# ST_LINK_V2-1_2.net
KiCad netlist of a schematic drawn in Altium Designer
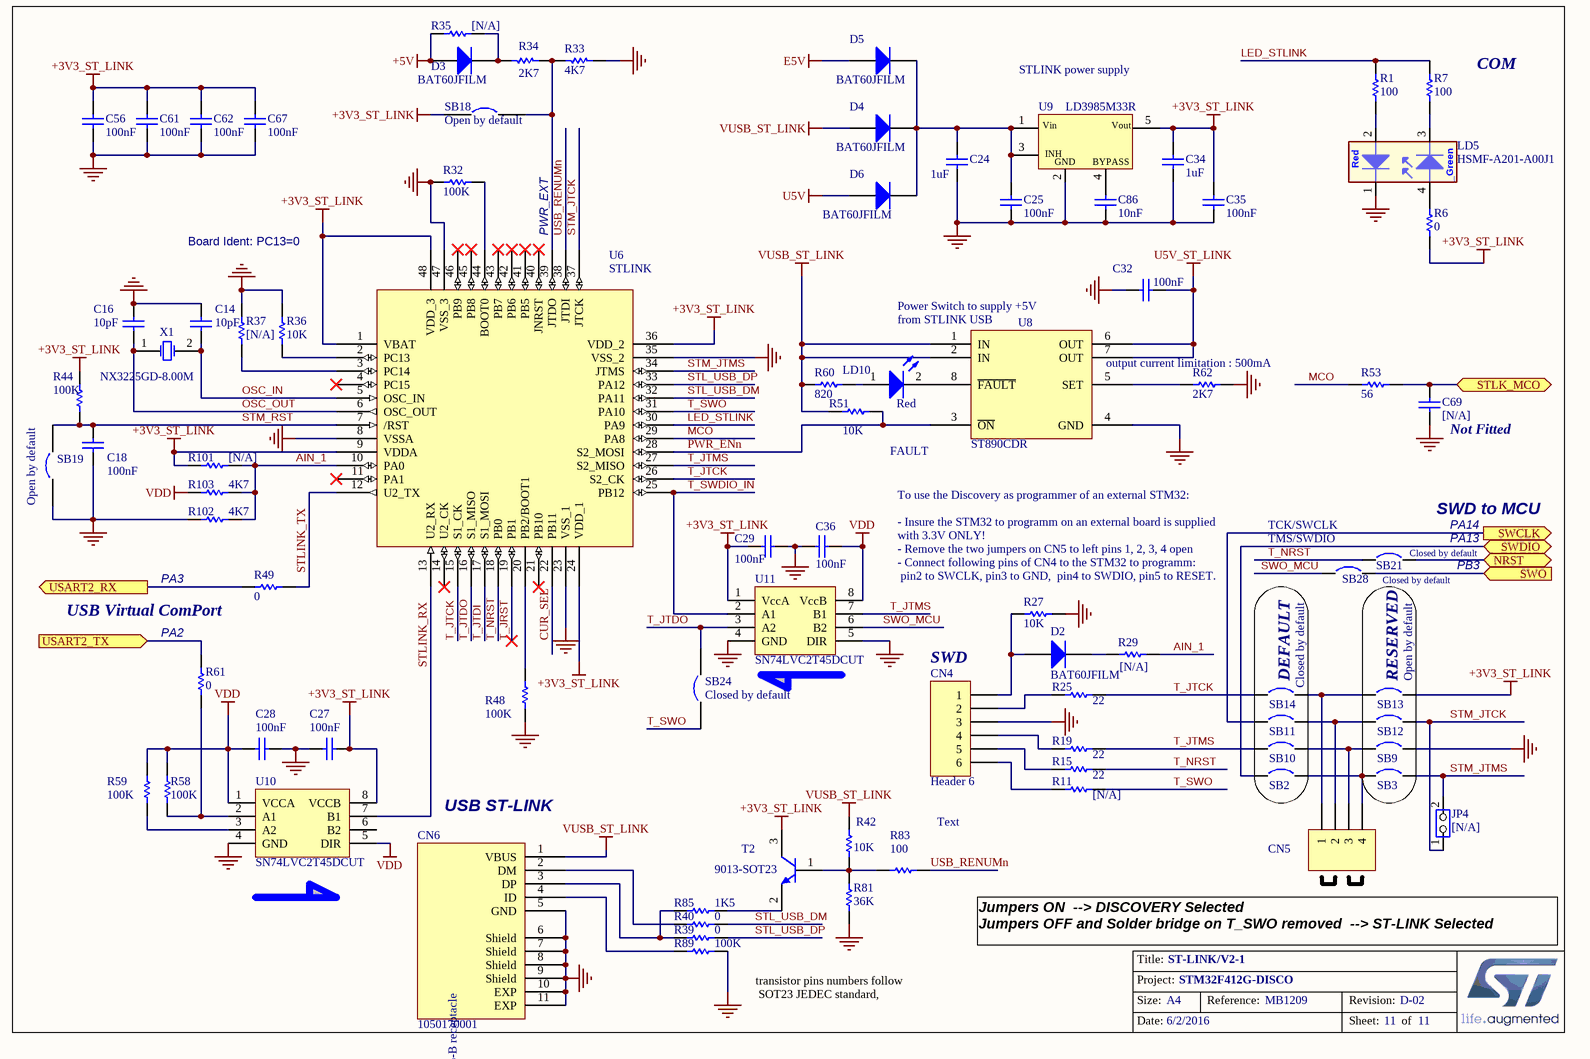
[diagram p0: ST_LINK_V2-1_2.SCHDOC]

(export (version "E")
  (design (tool "Eeschema 10.0.6"))
  (components
    (comp (ref "C14")
      (value "10pF")
      (footprint "0603C")
      (description "Capacitor 0402 / 0603 / 0805")
      (libsource (lib "MCD_TOOLS") (part "Capacitor_ST"))
    )
    (comp (ref "C16")
      (value "10pF")
      (footprint "0603C")
      (description "Capacitor 0402 / 0603 / 0805")
      (libsource (lib "MCD_TOOLS") (part "Capacitor_ST"))
    )
    (comp (ref "C18")
      (value "100nF")
      (footprint "0402C")
      (description "Capacitor 0402 / 0603 / 0805")
      (libsource (lib "MCD_TOOLS") (part "Capacitor_ST"))
    )
    (comp (ref "C24")
      (value "1uF")
      (footprint "0603C")
      (description "Capacitor")
      (fields (field (name "TOLERANCE") "10%"))
      (libsource (lib "MB963_1") (part "CAP SMD 0603  X5R 1µF 25V 10%"))
    )
    (comp (ref "C25")
      (value "100nF")
      (footprint "0402C")
      (description "Capacitor 0402 / 0603 / 0805")
      (libsource (lib "MCD_TOOLS") (part "Capacitor_ST"))
    )
    (comp (ref "C27")
      (value "100nF")
      (footprint "0402C")
      (description "Capacitor")
      (fields (field (name "PUBLISHER") "Altium Limited"))
      (libsource (lib "Miscellaneous Devices") (part "CAP"))
    )
    (comp (ref "C28")
      (value "100nF")
      (footprint "0402C")
      (description "Capacitor")
      (fields (field (name "PUBLISHER") "Altium Limited"))
      (libsource (lib "Miscellaneous Devices") (part "CAP"))
    )
    (comp (ref "C29")
      (value "100nF")
      (footprint "0402C")
      (description "Capacitor")
      (fields (field (name "PUBLISHER") "Altium Limited"))
      (libsource (lib "Miscellaneous Devices") (part "CAP"))
    )
    (comp (ref "C32")
      (value "100nF")
      (footprint "0402C")
      (description "Capacitor 0402 / 0603 / 0805")
      (libsource (lib "MCD_TOOLS") (part "Capacitor_ST"))
    )
    (comp (ref "C34")
      (value "1uF")
      (footprint "0603C")
      (description "Capacitor")
      (fields (field (name "TOLERANCE") "10%"))
      (libsource (lib "MB963_1") (part "CAP SMD 0603  X5R 1µF 25V 10%"))
    )
    (comp (ref "C35")
      (value "100nF")
      (footprint "0402C")
      (description "Capacitor 0402 / 0603 / 0805")
      (libsource (lib "MCD_TOOLS") (part "Capacitor_ST"))
    )
    (comp (ref "C36")
      (value "100nF")
      (footprint "0402C")
      (description "Capacitor")
      (fields (field (name "PUBLISHER") "Altium Limited"))
      (libsource (lib "Miscellaneous Devices") (part "CAP"))
    )
    (comp (ref "C56")
      (value "100nF")
      (footprint "0402C")
      (description "Capacitor 0402 / 0603 / 0805")
      (libsource (lib "MCD_TOOLS") (part "Capacitor_ST"))
    )
    (comp (ref "C61")
      (value "100nF")
      (footprint "0402C")
      (description "Capacitor 0402 / 0603 / 0805")
      (libsource (lib "MCD_TOOLS") (part "Capacitor_ST"))
    )
    (comp (ref "C62")
      (value "100nF")
      (footprint "0402C")
      (description "Capacitor 0402 / 0603 / 0805")
      (libsource (lib "MCD_TOOLS") (part "Capacitor_ST"))
    )
    (comp (ref "C67")
      (value "100nF")
      (footprint "0402C")
      (description "Capacitor 0402 / 0603 / 0805")
      (libsource (lib "MCD_TOOLS") (part "Capacitor_ST"))
    )
    (comp (ref "C69")
      (value "[N/A]")
      (footprint "0603C")
      (description "Capacitor,20pF,50V,NPO,5%,0402,YAGEO")
      (libsource (lib "MCD_TOOLS") (part "Cap_20pF_NPO_5%_0402"))
    )
    (comp (ref "C86")
      (value "10nF")
      (footprint "0603C")
      (description "0603  X7R 10NF")
      (fields (field (name "TOLERANCE") "10%"))
      (libsource (lib "MB963_1") (part "CAP SMD 0603  X7R 10000PF 50V 10%"))
    )
    (comp (ref "CN4")
      (value "Header 6")
      (footprint "HDR_1X6_2R54_W")
      (description "Header, 6-Pin")
      (fields (field (name "PUBLISHER") "Altium Limited"))
      (libsource (lib "Miscellaneous Connectors") (part "Header 6"))
    )
    (comp (ref "CN5")
      (value "Header 4")
      (footprint "HDR_1X4_2R54_W")
      (description "Header, 4-Pin")
      (fields (field (name "PUBLISHER") "Altium Limited"))
      (libsource (lib "MB963_1") (part "Header 4"))
    )
    (comp (ref "CN6")
      (value "1050170001")
      (footprint "Molex_1050170001")
      (libsource (lib "Smartphone_accessory") (part "1050170001"))
    )
    (comp (ref "D2")
      (value "BAT60JFILM")
      (footprint "SOD-323")
      (libsource (lib "MCD_TOOLS") (part "BAT60JFILM"))
    )
    (comp (ref "D3")
      (value "BAT60JFILM")
      (footprint "SOD-323")
      (libsource (lib "MCD_TOOLS") (part "BAT60JFILM"))
    )
    (comp (ref "D4")
      (value "BAT60JFILM")
      (footprint "SOD-323")
      (libsource (lib "MCD_TOOLS") (part "BAT60JFILM"))
    )
    (comp (ref "D5")
      (value "BAT60JFILM")
      (footprint "SOD-323")
      (libsource (lib "MCD_TOOLS") (part "BAT60JFILM"))
    )
    (comp (ref "D6")
      (value "BAT60JFILM")
      (footprint "SOD-323")
      (libsource (lib "MCD_TOOLS") (part "BAT60JFILM"))
    )
    (comp (ref "JP4") (value "[N/A]") (footprint "SIP2") (libsource (lib "Almos") (part "JP2")))
    (comp (ref "LD5")
      (value "HSMF-A201-A00J1")
      (footprint "LED2_3528")
      (description "Bicolor Led")
      (libsource (lib "MCD_TOOLS") (part "LD_BICOLOR_CMS"))
    )
    (comp (ref "LD10")
      (value "Red")
      (footprint "0603D")
      (description "Typical RED, GREEN, YELLOW, AMBER GaAs LED")
      (fields (field (name "SILKSCREEN") "FAULT") (field (name "PUBLISHER") "Altium Limited"))
      (libsource (lib "Miscellaneous Devices") (part "LED2"))
    )
    (comp (ref "R1")
      (value "100")
      (footprint "0402R")
      (description "Resistor")
      (fields (field (name "PUBLISHER") "Altium Limited"))
      (libsource (lib "") (part "Res1_1"))
    )
    (comp (ref "R6")
      (value "0")
      (footprint "SB_0603")
      (description "Resistor")
      (fields (field (name "PUBLISHER") "Altium Limited"))
      (libsource (lib "") (part "Res1_1"))
    )
    (comp (ref "R7")
      (value "100")
      (footprint "0402R")
      (description "Resistor")
      (fields (field (name "PUBLISHER") "Altium Limited"))
      (libsource (lib "") (part "Res1_1"))
    )
    (comp (ref "R11")
      (value "[N/A]")
      (footprint "0402R")
      (description "Resistor")
      (fields (field (name "PUBLISHER") "Altium Limited"))
      (libsource (lib "MB915_1") (part "res1"))
    )
    (comp (ref "R15")
      (value "22")
      (footprint "0402R")
      (description "Resistor")
      (fields (field (name "PUBLISHER") "Altium Limited"))
      (libsource (lib "MB915_1") (part "res1"))
    )
    (comp (ref "R19")
      (value "22")
      (footprint "0402R")
      (description "Resistor")
      (fields (field (name "PUBLISHER") "Altium Limited"))
      (libsource (lib "MB915_1") (part "res1"))
    )
    (comp (ref "R25")
      (value "22")
      (footprint "0402R")
      (description "Resistor")
      (fields (field (name "PUBLISHER") "Altium Limited"))
      (libsource (lib "MB915_1") (part "res1"))
    )
    (comp (ref "R27")
      (value "10K")
      (footprint "0402R")
      (description "Resistor")
      (fields (field (name "PUBLISHER") "Altium Limited"))
      (libsource (lib "MB915_1") (part "res1"))
    )
    (comp (ref "R29")
      (value "[N/A]")
      (footprint "STM-SMEE:0402R")
      (description "Resistor,[NA],0402")
      (libsource (lib "MCD_TOOLS") (part "Res_NA_0402"))
    )
    (comp (ref "R32")
      (value "100K")
      (footprint "0402R")
      (description "Resistor 0402 / 0603 / 0805")
      (libsource (lib "Miscellaneous Devices") (part "Res1"))
    )
    (comp (ref "R33")
      (value "4K7")
      (footprint "0603R")
      (description "Resistor")
      (fields (field (name "PUBLISHER") "Altium Limited"))
      (libsource (lib "") (part "Res1_2"))
    )
    (comp (ref "R34")
      (value "2K7")
      (footprint "0603R")
      (description "Resistor")
      (fields (field (name "PUBLISHER") "Altium Limited"))
      (libsource (lib "") (part "Res1_2"))
    )
    (comp (ref "R35")
      (value "[N/A]")
      (footprint "0402R")
      (description "Resistor")
      (libsource (lib "MCD_TOOLS") (part "Resistor_ST"))
    )
    (comp (ref "R36")
      (value "10K")
      (footprint "0402R")
      (description "Resistor")
      (libsource (lib "Miscellaneous Devices") (part "Res1"))
    )
    (comp (ref "R37")
      (value "[N/A]")
      (footprint "0603R")
      (description "Resistor 0402 / 0603 / 0805")
      (libsource (lib "Miscellaneous Devices") (part "Res1"))
    )
    (comp (ref "R39")
      (value "0")
      (footprint "SB_0603")
      (description "Resistor")
      (libsource (lib "Miscellaneous Devices") (part "Res1"))
    )
    (comp (ref "R40")
      (value "0")
      (footprint "SB_0603")
      (description "Resistor")
      (libsource (lib "Miscellaneous Devices") (part "Res1"))
    )
    (comp (ref "R42")
      (value "10K")
      (footprint "0402R")
      (description "Resistor")
      (fields (field (name "PUBLISHER") "Altium Limited"))
      (libsource (lib "") (part "Res1_1"))
    )
    (comp (ref "R44")
      (value "100K")
      (footprint "0402R")
      (description "Resistor 0402 / 0603 / 0805")
      (libsource (lib "Miscellaneous Devices") (part "Res1"))
    )
    (comp (ref "R48")
      (value "100K")
      (footprint "0402R")
      (description "Resistor 0402 / 0603 / 0805")
      (libsource (lib "Miscellaneous Devices") (part "Res1"))
    )
    (comp (ref "R49")
      (value "0")
      (footprint "SB_0603")
      (description "Resistor")
      (fields (field (name "PUBLISHER") "Altium Limited"))
      (libsource (lib "") (part "Res1_1"))
    )
    (comp (ref "R51")
      (value "10K")
      (footprint "0402R")
      (description "Resistor")
      (libsource (lib "MCD_TOOLS") (part "Resistor_ST"))
    )
    (comp (ref "R53")
      (value "56")
      (footprint "0603R")
      (description "Resistor")
      (fields (field (name "PUBLISHER") "Altium Limited"))
      (libsource (lib "") (part "Res1_1"))
    )
    (comp (ref "R58")
      (value "100K")
      (footprint "0402R")
      (description "Resistor")
      (fields (field (name "PUBLISHER") "Altium Limited"))
      (libsource (lib "") (part "Res1_1"))
    )
    (comp (ref "R59")
      (value "100K")
      (footprint "0402R")
      (description "Resistor")
      (fields (field (name "PUBLISHER") "Altium Limited"))
      (libsource (lib "") (part "Res1_1"))
    )
    (comp (ref "R60")
      (value "820")
      (footprint "0402R")
      (description "Resistor")
      (fields (field (name "PUBLISHER") "Altium Limited"))
      (libsource (lib "Miscellaneous Devices") (part "res1"))
    )
    (comp (ref "R61")
      (value "0")
      (footprint "SB_0603")
      (description "Resistor")
      (fields (field (name "PUBLISHER") "Altium Limited"))
      (libsource (lib "") (part "Res1_1"))
    )
    (comp (ref "R62")
      (value "2K7")
      (footprint "STM-SMEE:0603R")
      (description "Resistor 0402 / 0603 / 0805")
      (libsource (lib "MCD_TOOLS") (part "Resistor_ST"))
    )
    (comp (ref "R81")
      (value "36K")
      (footprint "0603R")
      (description "Resistor")
      (fields (field (name "PUBLISHER") "Altium Limited"))
      (libsource (lib "") (part "Res1_1"))
    )
    (comp (ref "R83")
      (value "100")
      (footprint "0402R")
      (description "Resistor 0402 / 0603 / 0805")
      (libsource (lib "Miscellaneous Devices") (part "Res1"))
    )
    (comp (ref "R85")
      (value "1K5")
      (footprint "0603R")
      (description "Resistor")
      (libsource (lib "Miscellaneous Devices") (part "Res1"))
    )
    (comp (ref "R89")
      (value "100K")
      (footprint "0402R")
      (description "Resistor")
      (fields (field (name "PUBLISHER") "Altium Limited"))
      (libsource (lib "Miscellaneous Devices") (part "res1"))
    )
    (comp (ref "R101")
      (value "[N/A]")
      (footprint "0603R")
      (description "Resistor 0402 / 0603 / 0805")
      (libsource (lib "Miscellaneous Devices") (part "Res1"))
    )
    (comp (ref "R102")
      (value "4K7")
      (footprint "0603R")
      (description "Resistor 0402 / 0603 / 0805")
      (libsource (lib "Miscellaneous Devices") (part "Res1"))
    )
    (comp (ref "R103")
      (value "4K7")
      (footprint "0603R")
      (description "Resistor 0402 / 0603 / 0805")
      (libsource (lib "Miscellaneous Devices") (part "Res1"))
    )
    (comp (ref "SB2")
      (value "Closed by default")
      (footprint "SB_0603")
      (description "Circuit Breaker")
      (libsource (lib "MCD_TOOLS") (part "Circuit Breaker"))
    )
    (comp (ref "SB3")
      (value "Open by default")
      (footprint "SB_0603")
      (description "Circuit Breaker")
      (libsource (lib "MCD_TOOLS") (part "Circuit Breaker"))
    )
    (comp (ref "SB9")
      (value "Open by default")
      (footprint "SB_0603")
      (description "Circuit Breaker")
      (libsource (lib "MCD_TOOLS") (part "Circuit Breaker"))
    )
    (comp (ref "SB10")
      (value "Closed by default")
      (footprint "SB_0603")
      (description "Circuit Breaker")
      (libsource (lib "MCD_TOOLS") (part "Circuit Breaker"))
    )
    (comp (ref "SB11")
      (value "Closed by default")
      (footprint "SB_0603")
      (description "Circuit Breaker")
      (libsource (lib "MCD_TOOLS") (part "Circuit Breaker"))
    )
    (comp (ref "SB12")
      (value "Open by default")
      (footprint "SB_0603")
      (description "Circuit Breaker")
      (libsource (lib "MCD_TOOLS") (part "Circuit Breaker"))
    )
    (comp (ref "SB13")
      (value "Open by default")
      (footprint "SB_0603")
      (description "Circuit Breaker")
      (libsource (lib "MCD_TOOLS") (part "Circuit Breaker"))
    )
    (comp (ref "SB14")
      (value "Closed by default")
      (footprint "SB_0603")
      (description "Circuit Breaker")
      (libsource (lib "MCD_TOOLS") (part "Circuit Breaker"))
    )
    (comp (ref "SB18")
      (value "Open by default")
      (footprint "SB_0603")
      (description "Circuit Breaker")
      (fields (field (name "PUBLISHER") "Altium Limited"))
      (libsource (lib "Miscellaneous Devices") (part "Circuit Breaker"))
    )
    (comp (ref "SB19")
      (value "Open by default")
      (footprint "SB_0603")
      (description "Circuit Breaker")
      (fields (field (name "PUBLISHER") "Altium Limited"))
      (libsource (lib "Miscellaneous Devices") (part "Circuit Breaker"))
    )
    (comp (ref "SB21")
      (value "Closed by default")
      (footprint "SB_0603")
      (description "Circuit Breaker")
      (libsource (lib "MCD_TOOLS") (part "Circuit Breaker"))
    )
    (comp (ref "SB24")
      (value "Closed by default")
      (footprint "SB_0603")
      (description "Circuit Breaker")
      (fields (field (name "PUBLISHER") "Altium Limited"))
      (libsource (lib "Miscellaneous Devices") (part "Circuit Breaker"))
    )
    (comp (ref "SB28")
      (value "Closed by default")
      (footprint "SB_0603")
      (description "Circuit Breaker")
      (libsource (lib "MCD_TOOLS") (part "Circuit Breaker"))
    )
    (comp (ref "T2")
      (value "9013-SOT23")
      (footprint "SOT-23")
      (description "NPN Bipolar Transistor")
      (fields (field (name "PUBLISHER") "Altium Limited"))
      (libsource (lib "MB1167") (part "NPN"))
    )
    (comp (ref "U6")
      (value "STLINK")
      (footprint "LQFP48_0R5_9X9")
      (libsource (lib "*") (part "STM32F10x(48pin)"))
    )
    (comp (ref "U8")
      (value "ST890CDR")
      (footprint "SOIC8_1R27_4R9X6")
      (libsource (lib "MB1167") (part "ST890CDR"))
    )
    (comp (ref "U9")
      (value "LD3985M33R")
      (footprint "SOT23-5")
      (description "Ultra low drop-low noise BiCMOS voltage, regulators low ESR capacitors compatible")
      (libsource (lib "MCD_TOOLS") (part "LD3985M33R"))
    )
    (comp (ref "U10")
      (value "SN74LVC2T45DCUT")
      (footprint "USOP8_0R5_2X3R1")
      (libsource (lib "MB818") (part "SN74LVC2T45DCUT"))
    )
    (comp (ref "U11")
      (value "SN74LVC2T45DCUT")
      (footprint "USOP8_0R5_2X3R1")
      (libsource (lib "STLINK") (part "SN74LVC2T45DCUT"))
    )
    (comp (ref "X1")
      (value "NX3225GD-8.00M")
      (footprint "XTAL_2SM_3R2X2R5")
      (description "Crystal 8Mhz, 8pF, -+50PPM, SMD")
      (libsource (lib "MCD_TOOLS") (part "XTAL_8M_NX3225GD"))
    )
  )
  (nets
    (net (code "1") (name "+3V3_ST_LINK") (class "Default")
      (node (ref "C27") (pin "1") (pinfunction "1_1") (pintype "passive"))
      (node (ref "C29") (pin "1") (pinfunction "1_1") (pintype "passive"))
      (node (ref "C34") (pin "1") (pinfunction "1_1") (pintype "passive"))
      (node (ref "C35") (pin "2") (pinfunction "2_2") (pintype "passive"))
      (node (ref "C56") (pin "2") (pinfunction "2_2") (pintype "passive"))
      (node (ref "C61") (pin "2") (pinfunction "2_2") (pintype "passive"))
      (node (ref "C62") (pin "2") (pinfunction "2_2") (pintype "passive"))
      (node (ref "C67") (pin "2") (pinfunction "2_2") (pintype "passive"))
      (node (ref "R101") (pin "1") (pinfunction "1_1") (pintype "passive"))
      (node (ref "R44") (pin "2") (pinfunction "2_2") (pintype "passive"))
      (node (ref "R6") (pin "2") (pinfunction "2_2") (pintype "passive"))
      (node (ref "SB13") (pin "2") (pinfunction "2_2") (pintype "passive"))
      (node (ref "SB18") (pin "1") (pinfunction "1_1") (pintype "passive"))
      (node (ref "T2") (pin "3") (pinfunction "C_3") (pintype "passive"))
      (node (ref "U10") (pin "8") (pinfunction "VCCB_8") (pintype "passive"))
      (node (ref "U11") (pin "1") (pinfunction "VccA_1") (pintype "passive"))
      (node (ref "U6") (pin "1") (pinfunction "VBAT_1") (pintype "power_in"))
      (node (ref "U6") (pin "24") (pinfunction "VDD_1_24") (pintype "power_in"))
      (node (ref "U6") (pin "36") (pinfunction "VDD_2_36") (pintype "power_in"))
      (node (ref "U6") (pin "48") (pinfunction "VDD_3_48") (pintype "power_in"))
      (node (ref "U6") (pin "9") (pinfunction "VDDA_9") (pintype "power_in"))
      (node (ref "U9") (pin "5") (pinfunction "Vout_5") (pintype "passive"))
    )
    (net (code "2") (name "+5V") (class "Default")
      (node (ref "D3") (pin "1") (pinfunction "A_1") (pintype "passive"))
      (node (ref "R35") (pin "1") (pinfunction "1_1") (pintype "passive"))
    )
    (net (code "3") (name "/AIN_1") (class "Default")
      (node (ref "R101") (pin "2") (pinfunction "2_2") (pintype "passive"))
      (node (ref "R102") (pin "2") (pinfunction "2_2") (pintype "passive"))
      (node (ref "R103") (pin "2") (pinfunction "2_2") (pintype "passive"))
      (node (ref "R29") (pin "2") (pinfunction "2_2") (pintype "passive"))
      (node (ref "U6") (pin "10") (pinfunction "PA0_10") (pintype "bidirectional"))
    )
    (net (code "4") (name "/CUR_SEL") (class "Default")
      (node (ref "U6") (pin "22") (pinfunction "PB11_22") (pintype "passive"))
    )
    (net (code "5") (name "/LED_STLINK") (class "Default")
      (node (ref "R1") (pin "1") (pinfunction "1_1") (pintype "passive"))
      (node (ref "R7") (pin "1") (pinfunction "1_1") (pintype "passive"))
      (node (ref "U6") (pin "30") (pinfunction "PA9_30") (pintype "bidirectional"))
    )
    (net (code "6") (name "/MCO") (class "Default")
      (node (ref "R53") (pin "2") (pinfunction "2_2") (pintype "passive"))
      (node (ref "U6") (pin "29") (pinfunction "PA8_29") (pintype "bidirectional"))
    )
    (net (code "7") (name "/NRST") (class "Default")
      (node (ref "SB21") (pin "2") (pinfunction "2_2") (pintype "passive"))
    )
    (net (code "8") (name "/OSC_IN") (class "Default")
      (node (ref "C14") (pin "1") (pinfunction "1_1") (pintype "passive"))
      (node (ref "U6") (pin "5") (pinfunction "OSC_IN_5") (pintype "input"))
      (node (ref "X1") (pin "2") (pinfunction "OSC2_2") (pintype "passive"))
    )
    (net (code "9") (name "/OSC_OUT") (class "Default")
      (node (ref "C16") (pin "1") (pinfunction "1_1") (pintype "passive"))
      (node (ref "U6") (pin "6") (pinfunction "OSC_OUT_6") (pintype "output"))
      (node (ref "X1") (pin "1") (pinfunction "OSC1_1") (pintype "passive"))
    )
    (net (code "10") (name "/PWR_ENn") (class "Default")
      (node (ref "R51") (pin "2") (pinfunction "2_2") (pintype "passive"))
      (node (ref "U6") (pin "28") (pinfunction "S2_MOSI_28") (pintype "bidirectional"))
      (node (ref "U8") (pin "3") (pinfunction "~{ON}_3") (pintype "passive"))
    )
    (net (code "11") (name "/STLINK_RX") (class "Default")
      (node (ref "U10") (pin "7") (pinfunction "B1_7") (pintype "passive"))
      (node (ref "U6") (pin "13") (pinfunction "U2_RX_13") (pintype "input"))
    )
    (net (code "12") (name "/STLINK_TX") (class "Default")
      (node (ref "R49") (pin "2") (pinfunction "2_2") (pintype "passive"))
      (node (ref "U6") (pin "12") (pinfunction "U2_TX_12") (pintype "output"))
    )
    (net (code "13") (name "/STLK_MCO") (class "Default")
      (node (ref "C69") (pin "1") (pinfunction "1_1") (pintype "passive"))
      (node (ref "R53") (pin "1") (pinfunction "1_1") (pintype "passive"))
    )
    (net (code "14") (name "/STL_USB_DM") (class "Default")
      (node (ref "R40") (pin "2") (pinfunction "2_2") (pintype "passive"))
      (node (ref "U6") (pin "32") (pinfunction "PA11_32") (pintype "bidirectional"))
    )
    (net (code "15") (name "/STL_USB_DP") (class "Default")
      (node (ref "R39") (pin "2") (pinfunction "2_2") (pintype "passive"))
      (node (ref "U6") (pin "33") (pinfunction "PA12_33") (pintype "bidirectional"))
    )
    (net (code "16") (name "/STM_JTCK") (class "Default")
      (node (ref "JP4") (pin "1") (pinfunction "COMMON_1") (pintype "passive"))
      (node (ref "SB12") (pin "2") (pinfunction "2_2") (pintype "passive"))
      (node (ref "U6") (pin "37") (pinfunction "JTCK_37") (pintype "bidirectional"))
    )
    (net (code "17") (name "/STM_JTMS") (class "Default")
      (node (ref "JP4") (pin "2") (pinfunction "NO_2") (pintype "passive"))
      (node (ref "SB3") (pin "2") (pinfunction "2_2") (pintype "passive"))
      (node (ref "U6") (pin "34") (pinfunction "JTMS_34") (pintype "bidirectional"))
    )
    (net (code "18") (name "/STM_RST") (class "Default")
      (node (ref "C18") (pin "2") (pinfunction "2_2") (pintype "passive"))
      (node (ref "R44") (pin "1") (pinfunction "1_1") (pintype "passive"))
      (node (ref "SB19") (pin "2") (pinfunction "2_2") (pintype "passive"))
      (node (ref "U6") (pin "7") (pinfunction "/RST_7") (pintype "input"))
    )
    (net (code "19") (name "/SWCLK") (class "Default")
      (node (ref "SB11") (pin "1") (pinfunction "1_1") (pintype "passive"))
    )
    (net (code "20") (name "/SWDIO") (class "Default")
      (node (ref "SB2") (pin "1") (pinfunction "1_1") (pintype "passive"))
    )
    (net (code "21") (name "/SWO") (class "Default")
      (node (ref "SB28") (pin "2") (pinfunction "2_2") (pintype "passive"))
    )
    (net (code "22") (name "/SWO_MCU") (class "Default")
      (node (ref "SB28") (pin "1") (pinfunction "1_1") (pintype "passive"))
      (node (ref "U11") (pin "6") (pinfunction "B2_6") (pintype "passive"))
    )
    (net (code "23") (name "/T_JRST") (class "Default")
      (node (ref "U6") (pin "19") (pinfunction "PB1_19") (pintype "bidirectional+no_connect"))
    )
    (net (code "24") (name "/T_JTCK") (class "Default")
      (node (ref "R25") (pin "2") (pinfunction "2_2") (pintype "passive"))
      (node (ref "SB14") (pin "1") (pinfunction "1_1") (pintype "passive"))
      (node (ref "U6") (pin "15") (pinfunction "S1_CK_15") (pintype "bidirectional"))
      (node (ref "U6") (pin "26") (pinfunction "S2_CK_26") (pintype "bidirectional"))
    )
    (net (code "25") (name "/T_JTDI") (class "Default")
      (node (ref "U6") (pin "17") (pinfunction "S1_MOSI_17") (pintype "bidirectional"))
    )
    (net (code "26") (name "/T_JTDO") (class "Default")
      (node (ref "SB24") (pin "2") (pinfunction "2_2") (pintype "passive"))
      (node (ref "U11") (pin "3") (pinfunction "A2_3") (pintype "passive"))
      (node (ref "U6") (pin "16") (pinfunction "S1_MISO_16") (pintype "bidirectional"))
    )
    (net (code "27") (name "/T_JTMS") (class "Default")
      (node (ref "R19") (pin "2") (pinfunction "2_2") (pintype "passive"))
      (node (ref "SB10") (pin "1") (pinfunction "1_1") (pintype "passive"))
      (node (ref "U11") (pin "7") (pinfunction "B1_7") (pintype "passive"))
      (node (ref "U6") (pin "27") (pinfunction "S2_MISO_27") (pintype "bidirectional"))
    )
    (net (code "28") (name "/T_NRST") (class "Default")
      (node (ref "R15") (pin "2") (pinfunction "2_2") (pintype "passive"))
      (node (ref "SB21") (pin "1") (pinfunction "1_1") (pintype "passive"))
      (node (ref "U6") (pin "18") (pinfunction "PB0_18") (pintype "bidirectional"))
    )
    (net (code "29") (name "/T_SWDIO_IN") (class "Default")
      (node (ref "U11") (pin "2") (pinfunction "A1_2") (pintype "passive"))
      (node (ref "U6") (pin "25") (pinfunction "PB12_25") (pintype "bidirectional"))
    )
    (net (code "30") (name "/T_SWO") (class "Default")
      (node (ref "R11") (pin "2") (pinfunction "2_2") (pintype "passive"))
      (node (ref "SB24") (pin "1") (pinfunction "1_1") (pintype "passive"))
      (node (ref "U6") (pin "31") (pinfunction "PA10_31") (pintype "bidirectional"))
    )
    (net (code "31") (name "/USART2_RX") (class "Default")
      (node (ref "R49") (pin "1") (pinfunction "1_1") (pintype "passive"))
    )
    (net (code "32") (name "/USART2_TX") (class "Default")
      (node (ref "R61") (pin "1") (pinfunction "1_1") (pintype "passive"))
    )
    (net (code "33") (name "/USB_RENUMn") (class "Default")
      (node (ref "R83") (pin "2") (pinfunction "2_2") (pintype "passive"))
      (node (ref "U6") (pin "38") (pinfunction "JTDI_38") (pintype "bidirectional"))
    )
    (net (code "34") (name "E5V") (class "Default")
      (node (ref "D5") (pin "1") (pinfunction "A_1") (pintype "passive"))
    )
    (net (code "35") (name "GND") (class "Default")
      (node (ref "C14") (pin "2") (pinfunction "2_2") (pintype "passive"))
      (node (ref "C16") (pin "2") (pinfunction "2_2") (pintype "passive"))
      (node (ref "C18") (pin "1") (pinfunction "1_1") (pintype "passive"))
      (node (ref "C24") (pin "1") (pinfunction "1_1") (pintype "passive"))
      (node (ref "C25") (pin "1") (pinfunction "1_1") (pintype "passive"))
      (node (ref "C27") (pin "2") (pinfunction "2_2") (pintype "passive"))
      (node (ref "C28") (pin "2") (pinfunction "2_2") (pintype "passive"))
      (node (ref "C29") (pin "2") (pinfunction "2_2") (pintype "passive"))
      (node (ref "C32") (pin "1") (pinfunction "1_1") (pintype "passive"))
      (node (ref "C34") (pin "2") (pinfunction "2_2") (pintype "passive"))
      (node (ref "C35") (pin "1") (pinfunction "1_1") (pintype "passive"))
      (node (ref "C36") (pin "1") (pinfunction "1_1") (pintype "passive"))
      (node (ref "C56") (pin "1") (pinfunction "1_1") (pintype "passive"))
      (node (ref "C61") (pin "1") (pinfunction "1_1") (pintype "passive"))
      (node (ref "C62") (pin "1") (pinfunction "1_1") (pintype "passive"))
      (node (ref "C67") (pin "1") (pinfunction "1_1") (pintype "passive"))
      (node (ref "C69") (pin "2") (pinfunction "2_2") (pintype "passive"))
      (node (ref "C86") (pin "1") (pinfunction "1_1") (pintype "passive"))
      (node (ref "CN4") (pin "3") (pinfunction "3_3") (pintype "passive"))
      (node (ref "CN6") (pin "10") (pinfunction "EXP_10") (pintype "passive"))
      (node (ref "CN6") (pin "11") (pinfunction "EXP_11") (pintype "passive"))
      (node (ref "CN6") (pin "5") (pinfunction "GND_5") (pintype "passive"))
      (node (ref "CN6") (pin "6") (pinfunction "Shield_6") (pintype "passive"))
      (node (ref "CN6") (pin "7") (pinfunction "Shield_7") (pintype "passive"))
      (node (ref "CN6") (pin "8") (pinfunction "Shield_8") (pintype "passive"))
      (node (ref "CN6") (pin "9") (pinfunction "Shield_9") (pintype "passive"))
      (node (ref "LD5") (pin "1") (pinfunction "1_1") (pintype "passive"))
      (node (ref "R102") (pin "1") (pinfunction "1_1") (pintype "passive"))
      (node (ref "R27") (pin "1") (pinfunction "1_1") (pintype "passive"))
      (node (ref "R32") (pin "1") (pinfunction "1_1") (pintype "passive"))
      (node (ref "R33") (pin "2") (pinfunction "2_2") (pintype "passive"))
      (node (ref "R36") (pin "1") (pinfunction "1_1") (pintype "passive"))
      (node (ref "R37") (pin "1") (pinfunction "1_1") (pintype "passive"))
      (node (ref "R48") (pin "1") (pinfunction "1_1") (pintype "passive"))
      (node (ref "R62") (pin "2") (pinfunction "2_2") (pintype "passive"))
      (node (ref "R81") (pin "1") (pinfunction "1_1") (pintype "passive"))
      (node (ref "R89") (pin "2") (pinfunction "2_2") (pintype "passive"))
      (node (ref "SB19") (pin "1") (pinfunction "1_1") (pintype "passive"))
      (node (ref "SB9") (pin "2") (pinfunction "2_2") (pintype "passive"))
      (node (ref "U10") (pin "4") (pinfunction "GND_4") (pintype "passive"))
      (node (ref "U11") (pin "4") (pinfunction "GND_4") (pintype "passive"))
      (node (ref "U11") (pin "5") (pinfunction "DIR_5") (pintype "passive"))
      (node (ref "U6") (pin "23") (pinfunction "VSS_1_23") (pintype "passive"))
      (node (ref "U6") (pin "35") (pinfunction "VSS_2_35") (pintype "passive"))
      (node (ref "U6") (pin "47") (pinfunction "VSS_3_47") (pintype "passive"))
      (node (ref "U6") (pin "8") (pinfunction "VSSA_8") (pintype "passive"))
      (node (ref "U8") (pin "4") (pinfunction "GND_4") (pintype "passive"))
      (node (ref "U9") (pin "2") (pinfunction "GND_2") (pintype "passive"))
    )
    (net (code "36") (name "Net-(CN4-Pad2)") (class "Default")
      (node (ref "CN4") (pin "2") (pinfunction "2_2") (pintype "passive"))
      (node (ref "R25") (pin "1") (pinfunction "1_1") (pintype "passive"))
    )
    (net (code "37") (name "Net-(CN4-Pad4)") (class "Default")
      (node (ref "CN4") (pin "4") (pinfunction "4_4") (pintype "passive"))
      (node (ref "R19") (pin "1") (pinfunction "1_1") (pintype "passive"))
    )
    (net (code "38") (name "Net-(CN4-Pad5)") (class "Default")
      (node (ref "CN4") (pin "5") (pinfunction "5_5") (pintype "passive"))
      (node (ref "R15") (pin "1") (pinfunction "1_1") (pintype "passive"))
    )
    (net (code "39") (name "Net-(CN4-Pad6)") (class "Default")
      (node (ref "CN4") (pin "6") (pinfunction "6_6") (pintype "passive"))
      (node (ref "R11") (pin "1") (pinfunction "1_1") (pintype "passive"))
    )
    (net (code "40") (name "Net-(CN5-Pad1)") (class "Default")
      (node (ref "CN5") (pin "1") (pinfunction "1_1") (pintype "passive"))
      (node (ref "SB13") (pin "1") (pinfunction "1_1") (pintype "passive"))
      (node (ref "SB14") (pin "2") (pinfunction "2_2") (pintype "passive"))
    )
    (net (code "41") (name "Net-(CN5-Pad2)") (class "Default")
      (node (ref "CN5") (pin "2") (pinfunction "2_2") (pintype "passive"))
      (node (ref "SB11") (pin "2") (pinfunction "2_2") (pintype "passive"))
      (node (ref "SB12") (pin "1") (pinfunction "1_1") (pintype "passive"))
    )
    (net (code "42") (name "Net-(CN5-Pad3)") (class "Default")
      (node (ref "CN5") (pin "3") (pinfunction "3_3") (pintype "passive"))
      (node (ref "SB10") (pin "2") (pinfunction "2_2") (pintype "passive"))
      (node (ref "SB9") (pin "1") (pinfunction "1_1") (pintype "passive"))
    )
    (net (code "43") (name "Net-(CN5-Pad4)") (class "Default")
      (node (ref "CN5") (pin "4") (pinfunction "4_4") (pintype "passive"))
      (node (ref "SB2") (pin "2") (pinfunction "2_2") (pintype "passive"))
      (node (ref "SB3") (pin "1") (pinfunction "1_1") (pintype "passive"))
    )
    (net (code "44") (name "Net-(CN6-DM)") (class "Default")
      (node (ref "CN6") (pin "2") (pinfunction "DM_2") (pintype "passive"))
      (node (ref "R40") (pin "1") (pinfunction "1_1") (pintype "passive"))
    )
    (net (code "45") (name "Net-(CN6-DP)") (class "Default")
      (node (ref "CN6") (pin "3") (pinfunction "DP_3") (pintype "passive"))
      (node (ref "R39") (pin "1") (pinfunction "1_1") (pintype "passive"))
      (node (ref "R85") (pin "1") (pinfunction "1_1") (pintype "passive"))
    )
    (net (code "46") (name "Net-(CN6-ID)") (class "Default")
      (node (ref "CN6") (pin "4") (pinfunction "ID_4") (pintype "passive"))
      (node (ref "R89") (pin "1") (pinfunction "1_1") (pintype "passive"))
    )
    (net (code "47") (name "Net-(D2-A)") (class "Default")
      (node (ref "CN4") (pin "1") (pinfunction "1_1") (pintype "passive"))
      (node (ref "D2") (pin "1") (pinfunction "A_1") (pintype "passive"))
      (node (ref "R27") (pin "2") (pinfunction "2_2") (pintype "passive"))
    )
    (net (code "48") (name "Net-(D2-K)") (class "Default")
      (node (ref "D2") (pin "2") (pinfunction "K_2") (pintype "passive"))
      (node (ref "R29") (pin "1") (pinfunction "1_1") (pintype "passive"))
    )
    (net (code "49") (name "Net-(D3-K)") (class "Default")
      (node (ref "D3") (pin "2") (pinfunction "K_2") (pintype "passive"))
      (node (ref "R34") (pin "1") (pinfunction "1_1") (pintype "passive"))
      (node (ref "R35") (pin "2") (pinfunction "2_2") (pintype "passive"))
    )
    (net (code "50") (name "Net-(D4-K)") (class "Default")
      (node (ref "C24") (pin "2") (pinfunction "2_2") (pintype "passive"))
      (node (ref "C25") (pin "2") (pinfunction "2_2") (pintype "passive"))
      (node (ref "D4") (pin "2") (pinfunction "K_2") (pintype "passive"))
      (node (ref "D5") (pin "2") (pinfunction "K_2") (pintype "passive"))
      (node (ref "D6") (pin "2") (pinfunction "K_2") (pintype "passive"))
      (node (ref "U9") (pin "1") (pinfunction "Vin_1") (pintype "passive"))
      (node (ref "U9") (pin "3") (pinfunction "CE_3") (pintype "passive"))
    )
    (net (code "51") (name "Net-(LD5-Pad2)") (class "Default")
      (node (ref "LD5") (pin "2") (pinfunction "2_2") (pintype "passive"))
      (node (ref "R1") (pin "2") (pinfunction "2_2") (pintype "passive"))
    )
    (net (code "52") (name "Net-(LD5-Pad3)") (class "Default")
      (node (ref "LD5") (pin "3") (pinfunction "3_3") (pintype "passive"))
      (node (ref "R7") (pin "2") (pinfunction "2_2") (pintype "passive"))
    )
    (net (code "53") (name "Net-(LD5-Pad4)") (class "Default")
      (node (ref "LD5") (pin "4") (pinfunction "4_4") (pintype "passive"))
      (node (ref "R6") (pin "1") (pinfunction "1_1") (pintype "passive"))
    )
    (net (code "54") (name "Net-(LD10-A)") (class "Default")
      (node (ref "LD10") (pin "1") (pinfunction "A_1") (pintype "passive"))
      (node (ref "R60") (pin "1") (pinfunction "1_1") (pintype "passive"))
    )
    (net (code "55") (name "Net-(LD10-K)") (class "Default")
      (node (ref "LD10") (pin "2") (pinfunction "K_2") (pintype "passive"))
      (node (ref "U8") (pin "8") (pinfunction "~{FAULT}_8") (pintype "passive"))
    )
    (net (code "56") (name "Net-(T2-B)") (class "Default")
      (node (ref "R42") (pin "1") (pinfunction "1_1") (pintype "passive"))
      (node (ref "R81") (pin "2") (pinfunction "2_2") (pintype "passive"))
      (node (ref "R83") (pin "1") (pinfunction "1_1") (pintype "passive"))
      (node (ref "T2") (pin "1") (pinfunction "B_1") (pintype "passive"))
    )
    (net (code "57") (name "Net-(T2-E)") (class "Default")
      (node (ref "R85") (pin "2") (pinfunction "2_2") (pintype "passive"))
      (node (ref "T2") (pin "2") (pinfunction "E_2") (pintype "passive"))
    )
    (net (code "58") (name "Net-(U6-BOOT0)") (class "Default")
      (node (ref "R32") (pin "2") (pinfunction "2_2") (pintype "passive"))
      (node (ref "U6") (pin "44") (pinfunction "BOOT0_44") (pintype "bidirectional"))
    )
    (net (code "59") (name "Net-(U6-JTDO)") (class "Default")
      (node (ref "R33") (pin "1") (pinfunction "1_1") (pintype "passive"))
      (node (ref "R34") (pin "2") (pinfunction "2_2") (pintype "passive"))
      (node (ref "SB18") (pin "2") (pinfunction "2_2") (pintype "passive"))
      (node (ref "U6") (pin "39") (pinfunction "JTDO_39") (pintype "bidirectional"))
    )
    (net (code "60") (name "Net-(U6-PB2{slash}BOOT1)") (class "Default")
      (node (ref "R48") (pin "2") (pinfunction "2_2") (pintype "passive"))
      (node (ref "U6") (pin "20") (pinfunction "PB2/BOOT1_20") (pintype "passive"))
    )
    (net (code "61") (name "Net-(U6-PC13)") (class "Default")
      (node (ref "R36") (pin "2") (pinfunction "2_2") (pintype "passive"))
      (node (ref "U6") (pin "2") (pinfunction "PC13_2") (pintype "bidirectional"))
    )
    (net (code "62") (name "Net-(U6-PC14)") (class "Default")
      (node (ref "R37") (pin "2") (pinfunction "2_2") (pintype "passive"))
      (node (ref "U6") (pin "3") (pinfunction "PC14_3") (pintype "bidirectional"))
    )
    (net (code "63") (name "Net-(U8-SET)") (class "Default")
      (node (ref "R62") (pin "1") (pinfunction "1_1") (pintype "passive"))
      (node (ref "U8") (pin "5") (pinfunction "SET_5") (pintype "passive"))
    )
    (net (code "64") (name "Net-(U9-BYPASS)") (class "Default")
      (node (ref "C86") (pin "2") (pinfunction "2_2") (pintype "passive"))
      (node (ref "U9") (pin "4") (pinfunction "BYPASS_4") (pintype "passive"))
    )
    (net (code "65") (name "Net-(U10-A1)") (class "Default")
      (node (ref "R58") (pin "2") (pinfunction "2_2") (pintype "passive"))
      (node (ref "R61") (pin "2") (pinfunction "2_2") (pintype "passive"))
      (node (ref "U10") (pin "2") (pinfunction "A1_2") (pintype "passive"))
    )
    (net (code "66") (name "Net-(U10-A2)") (class "Default")
      (node (ref "R59") (pin "2") (pinfunction "2_2") (pintype "passive"))
      (node (ref "U10") (pin "3") (pinfunction "A2_3") (pintype "passive"))
    )
    (net (code "67") (name "U5V") (class "Default")
      (node (ref "D6") (pin "1") (pinfunction "A_1") (pintype "passive"))
    )
    (net (code "68") (name "U5V_ST_LINK") (class "Default")
      (node (ref "C32") (pin "2") (pinfunction "2_2") (pintype "passive"))
      (node (ref "U8") (pin "6") (pinfunction "OUT_6") (pintype "passive"))
      (node (ref "U8") (pin "7") (pinfunction "OUT_7") (pintype "passive"))
    )
    (net (code "69") (name "VDD") (class "Default")
      (node (ref "C28") (pin "1") (pinfunction "1_1") (pintype "passive"))
      (node (ref "C36") (pin "2") (pinfunction "2_2") (pintype "passive"))
      (node (ref "R103") (pin "1") (pinfunction "1_1") (pintype "passive"))
      (node (ref "R58") (pin "1") (pinfunction "1_1") (pintype "passive"))
      (node (ref "R59") (pin "1") (pinfunction "1_1") (pintype "passive"))
      (node (ref "U10") (pin "1") (pinfunction "VCCA_1") (pintype "passive"))
      (node (ref "U10") (pin "5") (pinfunction "DIR_5") (pintype "passive"))
      (node (ref "U11") (pin "8") (pinfunction "VccB_8") (pintype "passive"))
    )
    (net (code "70") (name "VUSB_ST_LINK") (class "Default")
      (node (ref "CN6") (pin "1") (pinfunction "VBUS_1") (pintype "passive"))
      (node (ref "D4") (pin "1") (pinfunction "A_1") (pintype "passive"))
      (node (ref "R42") (pin "2") (pinfunction "2_2") (pintype "passive"))
      (node (ref "R51") (pin "1") (pinfunction "1_1") (pintype "passive"))
      (node (ref "R60") (pin "2") (pinfunction "2_2") (pintype "passive"))
      (node (ref "U8") (pin "1") (pinfunction "IN_1") (pintype "passive"))
      (node (ref "U8") (pin "2") (pinfunction "IN_2") (pintype "passive"))
    )
    (net (code "71") (name "unconnected-(U6-JNRST-Pad40)") (class "Default")
      (node (ref "U6") (pin "40") (pinfunction "JNRST_40") (pintype "bidirectional+no_connect"))
    )
    (net (code "72") (name "unconnected-(U6-PA1-Pad11)") (class "Default")
      (node (ref "U6") (pin "11") (pinfunction "PA1_11") (pintype "bidirectional+no_connect"))
    )
    (net (code "73") (name "unconnected-(U6-PB5-Pad41)") (class "Default")
      (node (ref "U6") (pin "41") (pinfunction "PB5_41") (pintype "bidirectional+no_connect"))
    )
    (net (code "74") (name "unconnected-(U6-PB6-Pad42)") (class "Default")
      (node (ref "U6") (pin "42") (pinfunction "PB6_42") (pintype "bidirectional+no_connect"))
    )
    (net (code "75") (name "unconnected-(U6-PB7-Pad43)") (class "Default")
      (node (ref "U6") (pin "43") (pinfunction "PB7_43") (pintype "bidirectional+no_connect"))
    )
    (net (code "76") (name "unconnected-(U6-PB8-Pad45)") (class "Default")
      (node (ref "U6") (pin "45") (pinfunction "PB8_45") (pintype "bidirectional+no_connect"))
    )
    (net (code "77") (name "unconnected-(U6-PB9-Pad46)") (class "Default")
      (node (ref "U6") (pin "46") (pinfunction "PB9_46") (pintype "bidirectional+no_connect"))
    )
    (net (code "78") (name "unconnected-(U6-PB10-Pad21)") (class "Default")
      (node (ref "U6") (pin "21") (pinfunction "PB10_21") (pintype "bidirectional+no_connect"))
    )
    (net (code "79") (name "unconnected-(U6-PC15-Pad4)") (class "Default")
      (node (ref "U6") (pin "4") (pinfunction "PC15_4") (pintype "bidirectional+no_connect"))
    )
    (net (code "80") (name "unconnected-(U6-U2_CK-Pad14)") (class "Default")
      (node (ref "U6") (pin "14") (pinfunction "U2_CK_14") (pintype "bidirectional+no_connect"))
    )
    (net (code "81") (name "unconnected-(U10-B2-Pad6)") (class "Default")
      (node (ref "U10") (pin "6") (pinfunction "B2_6") (pintype "passive"))
    )
  )
)
